# wsd_raspi_shield.net
KiCad netlist of a schematic drawn in EAGLE
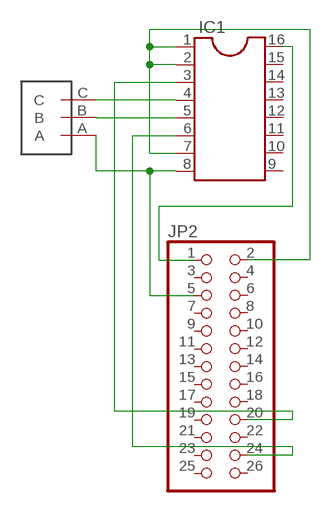
[diagram p0: schematic, sheet 1]

(export (version "E")
  (design (tool "Eeschema 10.0.6"))
  (components
    (comp (ref "IC1")
      (value "DIL16")
      (footprint "eagle-import:DIL16")
      (libsource (lib "eagle-import") (part "DIL16"))
    )
    (comp (ref "JP2")
      (value "PINHD-2X13")
      (footprint "eagle-import:2X13")
      (libsource (lib "eagle-import") (part "PINHD-2X13"))
    )
    (comp (ref "U$1")
      (value "TERMINALBLOCK_3P_3.5MM")
      (footprint "eagle-import:TERMINALBLOCK_3P_3.5MM")
      (libsource (lib "eagle-import") (part "TERMINALBLOCK_3P_3.5MM"))
    )
  )
  (nets
    (net (code "1") (name "Net-(IC1-Pad1)") (class "Default")
      (node (ref "IC1") (pin "1") (pinfunction "1_1") (pintype "passive"))
      (node (ref "IC1") (pin "2") (pinfunction "2_2") (pintype "passive"))
      (node (ref "IC1") (pin "7") (pinfunction "7_7") (pintype "passive"))
      (node (ref "JP2") (pin "2") (pinfunction "2_2") (pintype "passive"))
    )
    (net (code "2") (name "Net-(IC1-Pad3)") (class "Default")
      (node (ref "IC1") (pin "3") (pinfunction "3_3") (pintype "passive"))
      (node (ref "JP2") (pin "20") (pinfunction "20_20") (pintype "passive"))
    )
    (net (code "3") (name "Net-(IC1-Pad4)") (class "Default")
      (node (ref "IC1") (pin "4") (pinfunction "4_4") (pintype "passive"))
      (node (ref "U$1") (pin "C") (pinfunction "C_C") (pintype "bidirectional"))
    )
    (net (code "4") (name "Net-(IC1-Pad5)") (class "Default")
      (node (ref "IC1") (pin "5") (pinfunction "5_5") (pintype "passive"))
      (node (ref "U$1") (pin "B") (pinfunction "B_B") (pintype "bidirectional"))
    )
    (net (code "5") (name "Net-(IC1-Pad6)") (class "Default")
      (node (ref "IC1") (pin "6") (pinfunction "6_6") (pintype "passive"))
      (node (ref "JP2") (pin "24") (pinfunction "24_24") (pintype "passive"))
    )
    (net (code "6") (name "Net-(IC1-Pad8)") (class "Default")
      (node (ref "IC1") (pin "8") (pinfunction "8_8") (pintype "passive"))
      (node (ref "JP2") (pin "5") (pinfunction "5_5") (pintype "passive"))
      (node (ref "U$1") (pin "A") (pinfunction "A_A") (pintype "bidirectional"))
    )
    (net (code "7") (name "Net-(IC1-Pad16)") (class "Default")
      (node (ref "IC1") (pin "16") (pinfunction "16_16") (pintype "passive"))
      (node (ref "JP2") (pin "1") (pinfunction "1_1") (pintype "passive"))
    )
    (net (code "8") (name "unconnected-(IC1-Pad9)") (class "Default")
      (node (ref "IC1") (pin "9") (pinfunction "9_9") (pintype "passive"))
    )
    (net (code "9") (name "unconnected-(IC1-Pad10)") (class "Default")
      (node (ref "IC1") (pin "10") (pinfunction "10_10") (pintype "passive"))
    )
    (net (code "10") (name "unconnected-(IC1-Pad11)") (class "Default")
      (node (ref "IC1") (pin "11") (pinfunction "11_11") (pintype "passive"))
    )
    (net (code "11") (name "unconnected-(IC1-Pad12)") (class "Default")
      (node (ref "IC1") (pin "12") (pinfunction "12_12") (pintype "passive"))
    )
    (net (code "12") (name "unconnected-(IC1-Pad13)") (class "Default")
      (node (ref "IC1") (pin "13") (pinfunction "13_13") (pintype "passive"))
    )
    (net (code "13") (name "unconnected-(IC1-Pad14)") (class "Default")
      (node (ref "IC1") (pin "14") (pinfunction "14_14") (pintype "passive"))
    )
    (net (code "14") (name "unconnected-(IC1-Pad15)") (class "Default")
      (node (ref "IC1") (pin "15") (pinfunction "15_15") (pintype "passive"))
    )
    (net (code "15") (name "unconnected-(JP2-Pad3)") (class "Default")
      (node (ref "JP2") (pin "3") (pinfunction "3_3") (pintype "passive"))
    )
    (net (code "16") (name "unconnected-(JP2-Pad4)") (class "Default")
      (node (ref "JP2") (pin "4") (pinfunction "4_4") (pintype "passive"))
    )
    (net (code "17") (name "unconnected-(JP2-Pad6)") (class "Default")
      (node (ref "JP2") (pin "6") (pinfunction "6_6") (pintype "passive"))
    )
    (net (code "18") (name "unconnected-(JP2-Pad7)") (class "Default")
      (node (ref "JP2") (pin "7") (pinfunction "7_7") (pintype "passive"))
    )
    (net (code "19") (name "unconnected-(JP2-Pad8)") (class "Default")
      (node (ref "JP2") (pin "8") (pinfunction "8_8") (pintype "passive"))
    )
    (net (code "20") (name "unconnected-(JP2-Pad9)") (class "Default")
      (node (ref "JP2") (pin "9") (pinfunction "9_9") (pintype "passive"))
    )
    (net (code "21") (name "unconnected-(JP2-Pad10)") (class "Default")
      (node (ref "JP2") (pin "10") (pinfunction "10_10") (pintype "passive"))
    )
    (net (code "22") (name "unconnected-(JP2-Pad11)") (class "Default")
      (node (ref "JP2") (pin "11") (pinfunction "11_11") (pintype "passive"))
    )
    (net (code "23") (name "unconnected-(JP2-Pad12)") (class "Default")
      (node (ref "JP2") (pin "12") (pinfunction "12_12") (pintype "passive"))
    )
    (net (code "24") (name "unconnected-(JP2-Pad13)") (class "Default")
      (node (ref "JP2") (pin "13") (pinfunction "13_13") (pintype "passive"))
    )
    (net (code "25") (name "unconnected-(JP2-Pad14)") (class "Default")
      (node (ref "JP2") (pin "14") (pinfunction "14_14") (pintype "passive"))
    )
    (net (code "26") (name "unconnected-(JP2-Pad15)") (class "Default")
      (node (ref "JP2") (pin "15") (pinfunction "15_15") (pintype "passive"))
    )
    (net (code "27") (name "unconnected-(JP2-Pad16)") (class "Default")
      (node (ref "JP2") (pin "16") (pinfunction "16_16") (pintype "passive"))
    )
    (net (code "28") (name "unconnected-(JP2-Pad17)") (class "Default")
      (node (ref "JP2") (pin "17") (pinfunction "17_17") (pintype "passive"))
    )
    (net (code "29") (name "unconnected-(JP2-Pad18)") (class "Default")
      (node (ref "JP2") (pin "18") (pinfunction "18_18") (pintype "passive"))
    )
    (net (code "30") (name "unconnected-(JP2-Pad19)") (class "Default")
      (node (ref "JP2") (pin "19") (pinfunction "19_19") (pintype "passive"))
    )
    (net (code "31") (name "unconnected-(JP2-Pad21)") (class "Default")
      (node (ref "JP2") (pin "21") (pinfunction "21_21") (pintype "passive"))
    )
    (net (code "32") (name "unconnected-(JP2-Pad22)") (class "Default")
      (node (ref "JP2") (pin "22") (pinfunction "22_22") (pintype "passive"))
    )
    (net (code "33") (name "unconnected-(JP2-Pad23)") (class "Default")
      (node (ref "JP2") (pin "23") (pinfunction "23_23") (pintype "passive"))
    )
    (net (code "34") (name "unconnected-(JP2-Pad25)") (class "Default")
      (node (ref "JP2") (pin "25") (pinfunction "25_25") (pintype "passive"))
    )
    (net (code "35") (name "unconnected-(JP2-Pad26)") (class "Default")
      (node (ref "JP2") (pin "26") (pinfunction "26_26") (pintype "passive"))
    )
  )
)
